# Schematic2_second.net
KiCad netlist of a schematic drawn in Altium Designer
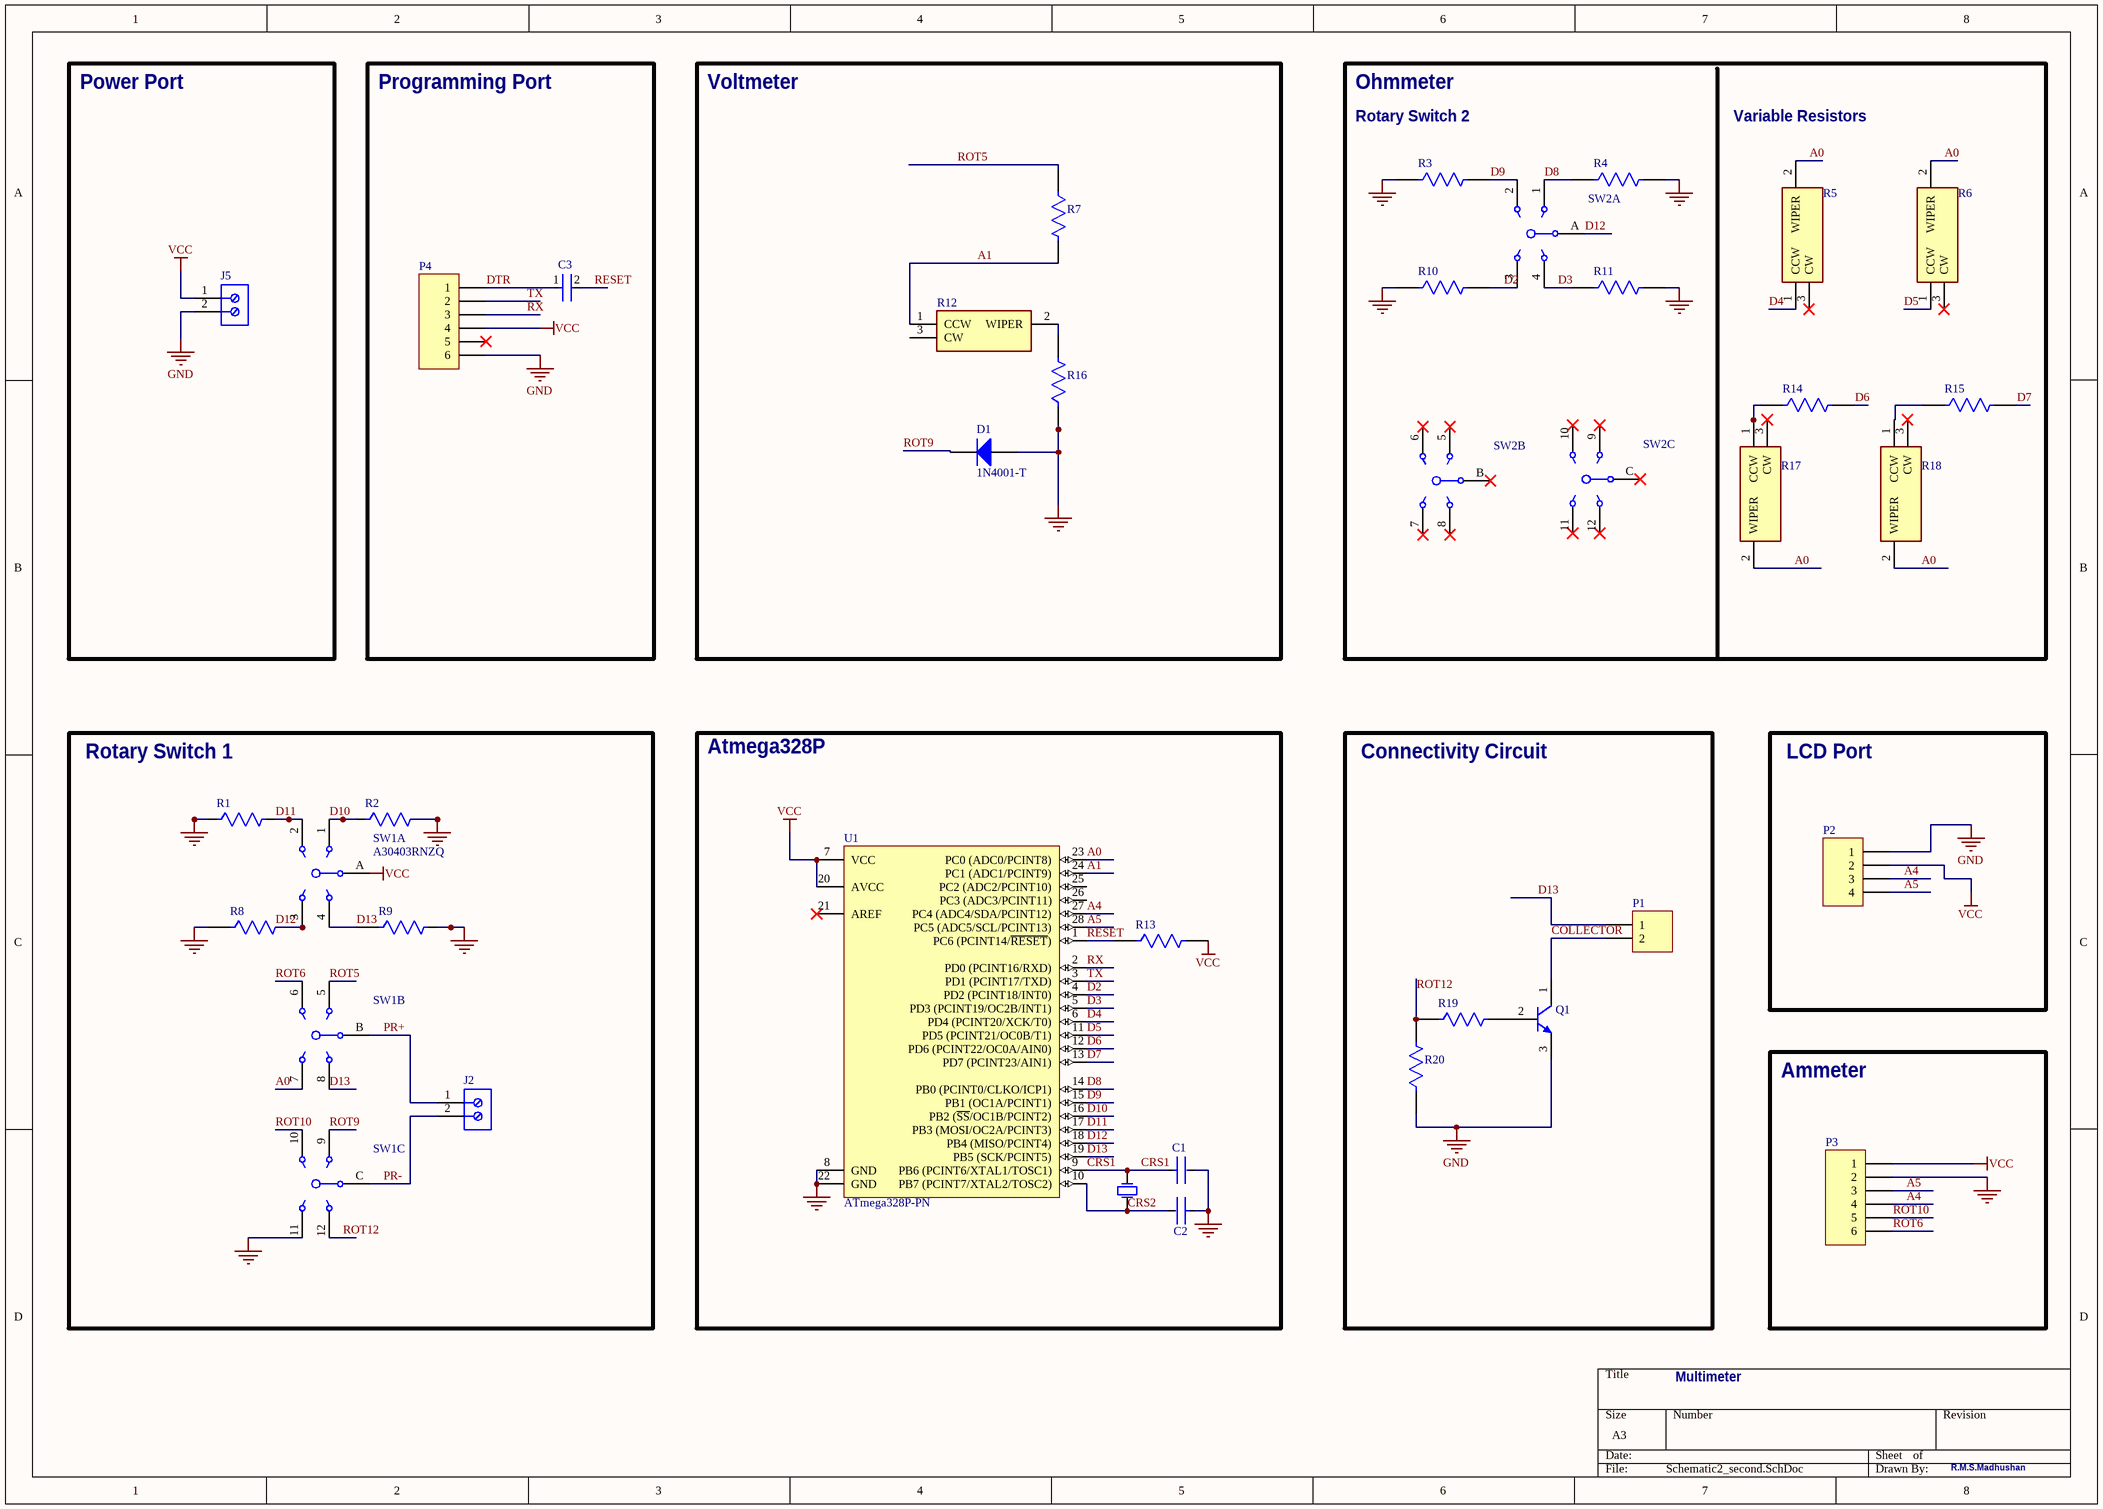
[diagram p0: Schematic2_second.SchDoc]

(export (version "E")
  (design (tool "Eeschema 10.0.6"))
  (components
    (comp (ref "C1")
      (value "RDE5C1H220J0K1H03B")
      (footprint "FP-RDE0M1-MFG")
      (description "Ceramic Capacitor 22pF ±5% 50V C0G Radial")
      (fields (field (name "TOLERANCE") "5%"))
      (libsource (lib "") (part "b4654b650e69147ec39a6b967a45e02_1"))
    )
    (comp (ref "C2")
      (value "RDE5C1H220J0K1H03B")
      (footprint "FP-RDE0M1-MFG")
      (description "Ceramic Capacitor 22pF ±5% 50V C0G Radial")
      (fields (field (name "TOLERANCE") "5%"))
      (libsource (lib "") (part "b4654b650e69147ec39a6b967a45e02_1"))
    )
    (comp (ref "C3")
      (value "RDE5C1H220J0K1H03B")
      (footprint "FP-RDE0M1-MFG")
      (description "Ceramic Capacitor 22pF ±5% 50V C0G Radial")
      (fields (field (name "TOLERANCE") "5%"))
      (libsource (lib "Altium Content Vault") (part "b4654b650e69147ec39a6b967a45e02"))
    )
    (comp (ref "D1")
      (value "1N4001-T")
      (footprint "DIOD-DO-41-P-2_V")
      (description "1.0 A Rectifier, 15 pF, 50 V, -65 to 150 degC, 2-Pin DO-41 Plastic, RoHS, Tape and Reel")
      (fields (field (name "MANUFACTURER") "Diodes Inc"))
      (libsource (lib "Altium Content Vault") (part "DIOD-D-A1K2-2"))
    )
    (comp (ref "J2")
      (value "691214110002")
      (footprint "691214110002")
      (description "Serie 2141 - 3.50 mm Horizontal Entry Modular with Rising Cage Clamp WR-TBL, 2 pin")
      (fields (field (name "MANUFACTURER") "Wurth Elektronik") (field (name "PUBLISHER") "WurthElektronik"))
      (libsource (lib "Altium Content Vault") (part "WE-CN-1P-F-TB2"))
    )
    (comp (ref "J5")
      (value "691214110002")
      (footprint "691214110002")
      (description "Serie 2141 - 3.50 mm Horizontal Entry Modular with Rising Cage Clamp WR-TBL, 2 pin")
      (fields (field (name "MANUFACTURER") "Wurth Elektronik") (field (name "PUBLISHER") "WurthElektronik"))
      (libsource (lib "Altium Content Vault") (part "WE-CN-1P-F-TB2"))
    )
    (comp (ref "P1")
      (value "Header 2")
      (footprint "MY_FE02W")
      (description "Header, 2-Pin")
      (fields (field (name "ASID PART NUMBER") "Header 2-AS"))
      (libsource (lib "Mylib+Rev+4") (part "Header 2"))
    )
    (comp (ref "P2")
      (value "Header 4")
      (footprint "MY_FE04W")
      (description "Header, 4-Pin")
      (fields (field (name "ASID PART NUMBER") "Header 4-AS"))
      (libsource (lib "Mylib+Rev+4") (part "Header 4"))
    )
    (comp (ref "P3")
      (value "Header 6")
      (footprint "MY_FE06W")
      (description "Header, 6-Pin")
      (fields (field (name "ASID PART NUMBER") "Header 6-AS"))
      (libsource (lib "Mylib+Rev+4") (part "Header 6"))
    )
    (comp (ref "P4")
      (value "Header 6")
      (footprint "MY_FE06W")
      (description "Header, 6-Pin")
      (fields (field (name "ASID PART NUMBER") "Header 6-AS"))
      (libsource (lib "Mylib+Rev+4") (part "Header 6"))
    )
    (comp (ref "Q1")
      (value "BC547BRL1G")
      (footprint "ONSC-TO-92-3-29-11_AM_BL")
      (description "Amplifier Transistor, NPN Silicon, 3-Pin TO-92, Pb-Free, Tape and Reel")
      (fields (field (name "MANUFACTURER") "On Semiconductor"))
      (libsource (lib "Altium Content Vault") (part "ONSC-NPN-C1B2E3-3"))
    )
    (comp (ref "R1")
      (value "G001R1000FE1280")
      (footprint "FP-G001R1000FE1280-MFG")
      (description "Res Wirewound 0.1 Ohm 1% 1W ±90ppm/°C Ceramic Hi Temp Sil AXL Thru-Hole Bulk")
      (fields (field (name "TOLERANCE") "1%"))
      (libsource (lib "Altium Content Vault") (part "1029c3af85768c4190bb7ad29bc67b5"))
    )
    (comp (ref "R2")
      (value "G001R1000FE1280")
      (footprint "FP-G001R1000FE1280-MFG")
      (description "Res Wirewound 0.1 Ohm 1% 1W ±90ppm/°C Ceramic Hi Temp Sil AXL Thru-Hole Bulk")
      (fields (field (name "TOLERANCE") "1%"))
      (libsource (lib "Altium Content Vault") (part "1029c3af85768c4190bb7ad29bc67b5"))
    )
    (comp (ref "R3")
      (value "G001R1000FE1280")
      (footprint "FP-G001R1000FE1280-MFG")
      (description "Res Wirewound 0.1 Ohm 1% 1W ±90ppm/°C Ceramic Hi Temp Sil AXL Thru-Hole Bulk")
      (fields (field (name "TOLERANCE") "1%"))
      (libsource (lib "Altium Content Vault") (part "1029c3af85768c4190bb7ad29bc67b5"))
    )
    (comp (ref "R4")
      (value "G001R1000FE1280")
      (footprint "FP-G001R1000FE1280-MFG")
      (description "Res Wirewound 0.1 Ohm 1% 1W ±90ppm/°C Ceramic Hi Temp Sil AXL Thru-Hole Bulk")
      (fields (field (name "TOLERANCE") "1%"))
      (libsource (lib "Altium Content Vault") (part "1029c3af85768c4190bb7ad29bc67b5"))
    )
    (comp (ref "R5")
      (value "3362P-1-203LF")
      (footprint "SamacSys:3362P_1")
      (description "Resistor")
      (fields (field (name "MOUSER PART NUMBER") "652-3362P-1-203LF"))
      (libsource (lib "*") (part "3362P-1-203LF"))
    )
    (comp (ref "R6")
      (value "3362P-1-203LF")
      (footprint "SamacSys:3362P_1")
      (description "Resistor")
      (fields (field (name "MOUSER PART NUMBER") "652-3362P-1-203LF"))
      (libsource (lib "*") (part "3362P-1-203LF"))
    )
    (comp (ref "R7")
      (value "G001R1000FE1280")
      (footprint "FP-G001R1000FE1280-MFG")
      (description "Res Wirewound 0.1 Ohm 1% 1W ±90ppm/°C Ceramic Hi Temp Sil AXL Thru-Hole Bulk")
      (fields (field (name "TOLERANCE") "1%"))
      (libsource (lib "Altium Content Vault") (part "1029c3af85768c4190bb7ad29bc67b5"))
    )
    (comp (ref "R8")
      (value "G001R1000FE1280")
      (footprint "FP-G001R1000FE1280-MFG")
      (description "Res Wirewound 0.1 Ohm 1% 1W ±90ppm/°C Ceramic Hi Temp Sil AXL Thru-Hole Bulk")
      (fields (field (name "TOLERANCE") "1%"))
      (libsource (lib "Altium Content Vault") (part "1029c3af85768c4190bb7ad29bc67b5"))
    )
    (comp (ref "R9")
      (value "G001R1000FE1280")
      (footprint "FP-G001R1000FE1280-MFG")
      (description "Res Wirewound 0.1 Ohm 1% 1W ±90ppm/°C Ceramic Hi Temp Sil AXL Thru-Hole Bulk")
      (fields (field (name "TOLERANCE") "1%"))
      (libsource (lib "Altium Content Vault") (part "1029c3af85768c4190bb7ad29bc67b5"))
    )
    (comp (ref "R10")
      (value "G001R1000FE1280")
      (footprint "FP-G001R1000FE1280-MFG")
      (description "Res Wirewound 0.1 Ohm 1% 1W ±90ppm/°C Ceramic Hi Temp Sil AXL Thru-Hole Bulk")
      (fields (field (name "TOLERANCE") "1%"))
      (libsource (lib "Altium Content Vault") (part "1029c3af85768c4190bb7ad29bc67b5"))
    )
    (comp (ref "R11")
      (value "G001R1000FE1280")
      (footprint "FP-G001R1000FE1280-MFG")
      (description "Res Wirewound 0.1 Ohm 1% 1W ±90ppm/°C Ceramic Hi Temp Sil AXL Thru-Hole Bulk")
      (fields (field (name "TOLERANCE") "1%"))
      (libsource (lib "Altium Content Vault") (part "1029c3af85768c4190bb7ad29bc67b5"))
    )
    (comp (ref "R12")
      (value "3362P-1-203LF")
      (footprint "SamacSys:3362P_1")
      (description "Resistor")
      (fields (field (name "MOUSER PART NUMBER") "652-3362P-1-203LF"))
      (libsource (lib "") (part "3362P-1-203LF_2"))
    )
    (comp (ref "R13")
      (value "G001R1000FE1280")
      (footprint "FP-G001R1000FE1280-MFG")
      (description "Res Wirewound 0.1 Ohm 1% 1W ±90ppm/°C Ceramic Hi Temp Sil AXL Thru-Hole Bulk")
      (fields (field (name "TOLERANCE") "1%"))
      (libsource (lib "Altium Content Vault") (part "1029c3af85768c4190bb7ad29bc67b5"))
    )
    (comp (ref "R14")
      (value "G001R1000FE1280")
      (footprint "FP-G001R1000FE1280-MFG")
      (description "Res Wirewound 0.1 Ohm 1% 1W ±90ppm/°C Ceramic Hi Temp Sil AXL Thru-Hole Bulk")
      (fields (field (name "TOLERANCE") "1%"))
      (libsource (lib "Altium Content Vault") (part "1029c3af85768c4190bb7ad29bc67b5"))
    )
    (comp (ref "R15")
      (value "G001R1000FE1280")
      (footprint "FP-G001R1000FE1280-MFG")
      (description "Res Wirewound 0.1 Ohm 1% 1W ±90ppm/°C Ceramic Hi Temp Sil AXL Thru-Hole Bulk")
      (fields (field (name "TOLERANCE") "1%"))
      (libsource (lib "Altium Content Vault") (part "1029c3af85768c4190bb7ad29bc67b5"))
    )
    (comp (ref "R16")
      (value "G001R1000FE1280")
      (footprint "FP-G001R1000FE1280-MFG")
      (description "Res Wirewound 0.1 Ohm 1% 1W ±90ppm/°C Ceramic Hi Temp Sil AXL Thru-Hole Bulk")
      (fields (field (name "TOLERANCE") "1%"))
      (libsource (lib "Altium Content Vault") (part "1029c3af85768c4190bb7ad29bc67b5"))
    )
    (comp (ref "R17")
      (value "3362P-1-203LF")
      (footprint "SamacSys:3362P_1")
      (description "Resistor")
      (fields (field (name "MOUSER PART NUMBER") "652-3362P-1-203LF"))
      (libsource (lib "") (part "3362P-1-203LF_1"))
    )
    (comp (ref "R18")
      (value "3362P-1-203LF")
      (footprint "SamacSys:3362P_1")
      (description "Resistor")
      (fields (field (name "MOUSER PART NUMBER") "652-3362P-1-203LF"))
      (libsource (lib "") (part "3362P-1-203LF_1"))
    )
    (comp (ref "R19")
      (value "G001R1000FE1280")
      (footprint "FP-G001R1000FE1280-MFG")
      (description "Res Wirewound 0.1 Ohm 1% 1W ±90ppm/°C Ceramic Hi Temp Sil AXL Thru-Hole Bulk")
      (fields (field (name "TOLERANCE") "1%"))
      (libsource (lib "Altium Content Vault") (part "1029c3af85768c4190bb7ad29bc67b5"))
    )
    (comp (ref "R20")
      (value "G001R1000FE1280")
      (footprint "FP-G001R1000FE1280-MFG")
      (description "Res Wirewound 0.1 Ohm 1% 1W ±90ppm/°C Ceramic Hi Temp Sil AXL Thru-Hole Bulk")
      (fields (field (name "TOLERANCE") "1%"))
      (libsource (lib "Altium Content Vault") (part "1029c3af85768c4190bb7ad29bc67b5"))
    )
    (comp (ref "SW1")
      (value "A30403RNZQ")
      (footprint "CKCP-A30403RNZQ-15_V")
      (description "A Series Rotary Switch, 3 Poles, 4 Positions, 30 deg Angle of Throw, -30 to 85 degC, RoHS")
      (fields (field (name "MANUFACTURER") "C&K Components"))
      (libsource (lib "Altium Content Vault") (part "CKCP-SW_3P4T-15"))
    )
    (comp (ref "SW2")
      (value "A30403RNZQ")
      (footprint "CKCP-A30403RNZQ-15_V")
      (description "A Series Rotary Switch, 3 Poles, 4 Positions, 30 deg Angle of Throw, -30 to 85 degC, RoHS")
      (fields (field (name "MANUFACTURER") "C&K Components"))
      (libsource (lib "Altium Content Vault") (part "CKCP-SW_3P4T-15"))
    )
    (comp (ref "U1")
      (value "ATmega328P-PN")
      (footprint "28P3")
      (libsource (lib "Altium Content Vault") (part "MC-8B-ATM48-IL28"))
    )
    (comp (ref "Y1")
      (value "FOXSLF/160-20")
      (footprint "FOX-FOXSLF160-20")
      (description "Resistance Weld Thru-Hole Crystal, 16 MHz, -20 to 70 degC, 2-Pin THD, RoHS, Bulk")
      (fields (field (name "TOLERANCE") "1%"))
      (libsource (lib "Altium Content Vault") (part "XTAL-1-2-2"))
    )
  )
  (nets
    (net (code "2") (name "/A0") (class "Default")
      (node (ref "R17") (pin "2") (pinfunction "WIPER_2") (pintype "passive"))
      (node (ref "R18") (pin "2") (pinfunction "WIPER_2") (pintype "passive"))
      (node (ref "R5") (pin "2") (pinfunction "WIPER_2") (pintype "passive"))
      (node (ref "R6") (pin "2") (pinfunction "WIPER_2") (pintype "passive"))
      (node (ref "SW1") (pin "7") (pinfunction "7_7") (pintype "passive"))
      (node (ref "U1") (pin "23") (pinfunction "PC0_(ADC0/PCINT8)_23") (pintype "bidirectional"))
    )
    (net (code "3") (name "/A1") (class "Default")
      (node (ref "R12") (pin "1") (pinfunction "CCW_1") (pintype "passive"))
      (node (ref "R7") (pin "2") (pinfunction "2_2") (pintype "passive"))
      (node (ref "U1") (pin "24") (pinfunction "PC1_(ADC1/PCINT9)_24") (pintype "bidirectional"))
    )
    (net (code "4") (name "/A4") (class "Default")
      (node (ref "P2") (pin "3") (pinfunction "3_3") (pintype "passive"))
      (node (ref "P3") (pin "4") (pinfunction "4_4") (pintype "passive"))
      (node (ref "U1") (pin "27") (pinfunction "PC4_(ADC4/SDA/PCINT12)_27") (pintype "bidirectional"))
    )
    (net (code "5") (name "/A5") (class "Default")
      (node (ref "P2") (pin "4") (pinfunction "4_4") (pintype "passive"))
      (node (ref "P3") (pin "3") (pinfunction "3_3") (pintype "passive"))
      (node (ref "U1") (pin "28") (pinfunction "PC5_(ADC5/SCL/PCINT13)_28") (pintype "bidirectional"))
    )
    (net (code "6") (name "/COLLECTOR") (class "Default")
      (node (ref "P1") (pin "2") (pinfunction "2_2") (pintype "passive"))
      (node (ref "Q1") (pin "1") (pinfunction "C_1") (pintype "passive"))
    )
    (net (code "7") (name "/CRS1") (class "Default")
      (node (ref "C1") (pin "1") (pinfunction "1_1") (pintype "passive"))
      (node (ref "U1") (pin "9") (pinfunction "PB6_(PCINT6/XTAL1/TOSC1)_9") (pintype "bidirectional"))
      (node (ref "Y1") (pin "1") (pinfunction "1_1") (pintype "passive"))
    )
    (net (code "8") (name "/CRS2") (class "Default")
      (node (ref "C2") (pin "2") (pinfunction "2_2") (pintype "passive"))
      (node (ref "U1") (pin "10") (pinfunction "PB7_(PCINT7/XTAL2/TOSC2)_10") (pintype "bidirectional"))
      (node (ref "Y1") (pin "2") (pinfunction "2_2") (pintype "passive"))
    )
    (net (code "9") (name "/D2") (class "Default")
      (node (ref "R10") (pin "2") (pinfunction "2_2") (pintype "passive"))
      (node (ref "SW2") (pin "3") (pinfunction "3_3") (pintype "passive"))
      (node (ref "U1") (pin "4") (pinfunction "PD2_(PCINT18/INT0)_4") (pintype "bidirectional"))
    )
    (net (code "10") (name "/D3") (class "Default")
      (node (ref "R11") (pin "1") (pinfunction "1_1") (pintype "passive"))
      (node (ref "SW2") (pin "4") (pinfunction "4_4") (pintype "passive"))
      (node (ref "U1") (pin "5") (pinfunction "PD3_(PCINT19/OC2B/INT1)_5") (pintype "bidirectional"))
    )
    (net (code "11") (name "/D4") (class "Default")
      (node (ref "R5") (pin "1") (pinfunction "CCW_1") (pintype "passive"))
      (node (ref "U1") (pin "6") (pinfunction "PD4_(PCINT20/XCK/T0)_6") (pintype "bidirectional"))
    )
    (net (code "12") (name "/D5") (class "Default")
      (node (ref "R6") (pin "1") (pinfunction "CCW_1") (pintype "passive"))
      (node (ref "U1") (pin "11") (pinfunction "PD5_(PCINT21/OC0B/T1)_11") (pintype "bidirectional"))
    )
    (net (code "13") (name "/D6") (class "Default")
      (node (ref "R14") (pin "2") (pinfunction "2_2") (pintype "passive"))
      (node (ref "U1") (pin "12") (pinfunction "PD6_(PCINT22/OC0A/AIN0)_12") (pintype "bidirectional"))
    )
    (net (code "14") (name "/D7") (class "Default")
      (node (ref "R15") (pin "2") (pinfunction "2_2") (pintype "passive"))
      (node (ref "U1") (pin "13") (pinfunction "PD7_(PCINT23/AIN1)_13") (pintype "bidirectional"))
    )
    (net (code "15") (name "/D8") (class "Default")
      (node (ref "R4") (pin "1") (pinfunction "1_1") (pintype "passive"))
      (node (ref "SW2") (pin "1") (pinfunction "1_1") (pintype "passive"))
      (node (ref "U1") (pin "14") (pinfunction "PB0_(PCINT0/CLKO/ICP1)_14") (pintype "bidirectional"))
    )
    (net (code "16") (name "/D9") (class "Default")
      (node (ref "R3") (pin "2") (pinfunction "2_2") (pintype "passive"))
      (node (ref "SW2") (pin "2") (pinfunction "2_2") (pintype "passive"))
      (node (ref "U1") (pin "15") (pinfunction "PB1_(OC1A/PCINT1)_15") (pintype "bidirectional"))
    )
    (net (code "17") (name "/D10") (class "Default")
      (node (ref "R2") (pin "1") (pinfunction "1_1") (pintype "passive"))
      (node (ref "SW1") (pin "1") (pinfunction "1_1") (pintype "passive"))
      (node (ref "U1") (pin "16") (pinfunction "PB2_(~{SS}/OC1B/PCINT2)_16") (pintype "bidirectional"))
    )
    (net (code "18") (name "/D11") (class "Default")
      (node (ref "R1") (pin "2") (pinfunction "2_2") (pintype "passive"))
      (node (ref "SW1") (pin "2") (pinfunction "2_2") (pintype "passive"))
      (node (ref "U1") (pin "17") (pinfunction "PB3_(MOSI/OC2A/PCINT3)_17") (pintype "bidirectional"))
    )
    (net (code "19") (name "/D12") (class "Default")
      (node (ref "R8") (pin "2") (pinfunction "2_2") (pintype "passive"))
      (node (ref "SW1") (pin "3") (pinfunction "3_3") (pintype "passive"))
      (node (ref "SW2") (pin "A") (pinfunction "A_A") (pintype "passive"))
      (node (ref "U1") (pin "18") (pinfunction "PB4_(MISO/PCINT4)_18") (pintype "bidirectional"))
    )
    (net (code "20") (name "/D13") (class "Default")
      (node (ref "P1") (pin "1") (pinfunction "1_1") (pintype "passive"))
      (node (ref "R9") (pin "1") (pinfunction "1_1") (pintype "passive"))
      (node (ref "SW1") (pin "4") (pinfunction "4_4") (pintype "passive"))
      (node (ref "SW1") (pin "8") (pinfunction "8_8") (pintype "passive"))
      (node (ref "U1") (pin "19") (pinfunction "PB5_(SCK/PCINT5)_19") (pintype "bidirectional"))
    )
    (net (code "21") (name "/DTR") (class "Default")
      (node (ref "C3") (pin "1") (pinfunction "1_1") (pintype "passive"))
      (node (ref "P4") (pin "1") (pinfunction "1_1") (pintype "passive"))
    )
    (net (code "22") (name "/PR+") (class "Default")
      (node (ref "J2") (pin "1") (pinfunction "1_1") (pintype "passive"))
      (node (ref "SW1") (pin "B") (pinfunction "B_B") (pintype "passive"))
    )
    (net (code "23") (name "/PR-") (class "Default")
      (node (ref "J2") (pin "2") (pinfunction "2_2") (pintype "passive"))
      (node (ref "SW1") (pin "C") (pinfunction "C_C") (pintype "passive"))
    )
    (net (code "24") (name "/RESET") (class "Default")
      (node (ref "C3") (pin "2") (pinfunction "2_2") (pintype "passive"))
      (node (ref "R13") (pin "1") (pinfunction "1_1") (pintype "passive"))
      (node (ref "U1") (pin "1") (pinfunction "PC6_(PCINT14/~{RESET})_1") (pintype "bidirectional"))
    )
    (net (code "25") (name "/ROT5") (class "Default")
      (node (ref "R7") (pin "1") (pinfunction "1_1") (pintype "passive"))
      (node (ref "SW1") (pin "5") (pinfunction "5_5") (pintype "passive"))
    )
    (net (code "26") (name "/ROT6") (class "Default")
      (node (ref "P3") (pin "6") (pinfunction "6_6") (pintype "passive"))
      (node (ref "SW1") (pin "6") (pinfunction "6_6") (pintype "passive"))
    )
    (net (code "27") (name "/ROT9") (class "Default")
      (node (ref "D1") (pin "2") (pinfunction "K_2") (pintype "passive"))
      (node (ref "SW1") (pin "9") (pinfunction "9_9") (pintype "passive"))
    )
    (net (code "28") (name "/ROT10") (class "Default")
      (node (ref "P3") (pin "5") (pinfunction "5_5") (pintype "passive"))
      (node (ref "SW1") (pin "10") (pinfunction "10_10") (pintype "passive"))
    )
    (net (code "29") (name "/ROT12") (class "Default")
      (node (ref "R19") (pin "1") (pinfunction "1_1") (pintype "passive"))
      (node (ref "R20") (pin "2") (pinfunction "2_2") (pintype "passive"))
      (node (ref "SW1") (pin "12") (pinfunction "12_12") (pintype "passive"))
    )
    (net (code "30") (name "/RX") (class "Default")
      (node (ref "P4") (pin "3") (pinfunction "3_3") (pintype "passive"))
      (node (ref "U1") (pin "2") (pinfunction "PD0_(PCINT16/RXD)_2") (pintype "bidirectional"))
    )
    (net (code "31") (name "/TX") (class "Default")
      (node (ref "P4") (pin "2") (pinfunction "2_2") (pintype "passive"))
      (node (ref "U1") (pin "3") (pinfunction "PD1_(PCINT17/TXD)_3") (pintype "bidirectional"))
    )
    (net (code "32") (name "GND") (class "Default")
      (node (ref "C1") (pin "2") (pinfunction "2_2") (pintype "passive"))
      (node (ref "C2") (pin "1") (pinfunction "1_1") (pintype "passive"))
      (node (ref "D1") (pin "1") (pinfunction "A_1") (pintype "passive"))
      (node (ref "J5") (pin "2") (pinfunction "2_2") (pintype "passive"))
      (node (ref "P2") (pin "1") (pinfunction "1_1") (pintype "passive"))
      (node (ref "P3") (pin "2") (pinfunction "2_2") (pintype "passive"))
      (node (ref "P4") (pin "6") (pinfunction "6_6") (pintype "passive"))
      (node (ref "Q1") (pin "3") (pinfunction "E_3") (pintype "passive"))
      (node (ref "R1") (pin "1") (pinfunction "1_1") (pintype "passive"))
      (node (ref "R10") (pin "1") (pinfunction "1_1") (pintype "passive"))
      (node (ref "R11") (pin "2") (pinfunction "2_2") (pintype "passive"))
      (node (ref "R16") (pin "1") (pinfunction "1_1") (pintype "passive"))
      (node (ref "R2") (pin "2") (pinfunction "2_2") (pintype "passive"))
      (node (ref "R20") (pin "1") (pinfunction "1_1") (pintype "passive"))
      (node (ref "R3") (pin "1") (pinfunction "1_1") (pintype "passive"))
      (node (ref "R4") (pin "2") (pinfunction "2_2") (pintype "passive"))
      (node (ref "R8") (pin "1") (pinfunction "1_1") (pintype "passive"))
      (node (ref "R9") (pin "2") (pinfunction "2_2") (pintype "passive"))
      (node (ref "SW1") (pin "11") (pinfunction "11_11") (pintype "passive"))
      (node (ref "U1") (pin "22") (pinfunction "GND_22") (pintype "power_in"))
      (node (ref "U1") (pin "8") (pinfunction "GND_8") (pintype "power_in"))
    )
    (net (code "33") (name "Net-(Q1-B)") (class "Default")
      (node (ref "Q1") (pin "2") (pinfunction "B_2") (pintype "passive"))
      (node (ref "R19") (pin "2") (pinfunction "2_2") (pintype "passive"))
    )
    (net (code "34") (name "Net-(R12-WIPER)") (class "Default")
      (node (ref "R12") (pin "2") (pinfunction "WIPER_2") (pintype "passive"))
      (node (ref "R16") (pin "2") (pinfunction "2_2") (pintype "passive"))
    )
    (net (code "35") (name "Net-(R17-CCW)") (class "Default")
      (node (ref "R14") (pin "1") (pinfunction "1_1") (pintype "passive"))
      (node (ref "R17") (pin "1") (pinfunction "CCW_1") (pintype "passive"))
    )
    (net (code "36") (name "Net-(R18-CCW)") (class "Default")
      (node (ref "R15") (pin "1") (pinfunction "1_1") (pintype "passive"))
      (node (ref "R18") (pin "1") (pinfunction "CCW_1") (pintype "passive"))
    )
    (net (code "37") (name "VCC") (class "Default")
      (node (ref "J5") (pin "1") (pinfunction "1_1") (pintype "passive"))
      (node (ref "P2") (pin "2") (pinfunction "2_2") (pintype "passive"))
      (node (ref "P3") (pin "1") (pinfunction "1_1") (pintype "passive"))
      (node (ref "P4") (pin "4") (pinfunction "4_4") (pintype "passive"))
      (node (ref "R13") (pin "2") (pinfunction "2_2") (pintype "passive"))
      (node (ref "SW1") (pin "A") (pinfunction "A_A") (pintype "passive"))
      (node (ref "U1") (pin "20") (pinfunction "AVCC_20") (pintype "power_in"))
      (node (ref "U1") (pin "7") (pinfunction "VCC_7") (pintype "power_in"))
    )
    (net (code "38") (name "unconnected-(P4-Pad5)") (class "Default")
      (node (ref "P4") (pin "5") (pinfunction "5_5") (pintype "passive+no_connect"))
    )
    (net (code "39") (name "unconnected-(R5-CW-Pad3)") (class "Default")
      (node (ref "R5") (pin "3") (pinfunction "CW_3") (pintype "passive+no_connect"))
    )
    (net (code "40") (name "unconnected-(R6-CW-Pad3)") (class "Default")
      (node (ref "R6") (pin "3") (pinfunction "CW_3") (pintype "passive+no_connect"))
    )
    (net (code "41") (name "unconnected-(R12-CW-Pad3)") (class "Default")
      (node (ref "R12") (pin "3") (pinfunction "CW_3") (pintype "passive"))
    )
    (net (code "42") (name "unconnected-(R17-CW-Pad3)") (class "Default")
      (node (ref "R17") (pin "3") (pinfunction "CW_3") (pintype "passive+no_connect"))
    )
    (net (code "43") (name "unconnected-(R18-CW-Pad3)") (class "Default")
      (node (ref "R18") (pin "3") (pinfunction "CW_3") (pintype "passive+no_connect"))
    )
    (net (code "44") (name "unconnected-(SW2-Pad5)") (class "Default")
      (node (ref "SW2") (pin "5") (pinfunction "5_5") (pintype "passive+no_connect"))
    )
    (net (code "45") (name "unconnected-(SW2-Pad6)") (class "Default")
      (node (ref "SW2") (pin "6") (pinfunction "6_6") (pintype "passive+no_connect"))
    )
    (net (code "46") (name "unconnected-(SW2-Pad7)") (class "Default")
      (node (ref "SW2") (pin "7") (pinfunction "7_7") (pintype "passive+no_connect"))
    )
    (net (code "47") (name "unconnected-(SW2-Pad8)") (class "Default")
      (node (ref "SW2") (pin "8") (pinfunction "8_8") (pintype "passive+no_connect"))
    )
    (net (code "48") (name "unconnected-(SW2-Pad9)") (class "Default")
      (node (ref "SW2") (pin "9") (pinfunction "9_9") (pintype "passive+no_connect"))
    )
    (net (code "49") (name "unconnected-(SW2-Pad10)") (class "Default")
      (node (ref "SW2") (pin "10") (pinfunction "10_10") (pintype "passive+no_connect"))
    )
    (net (code "50") (name "unconnected-(SW2-Pad11)") (class "Default")
      (node (ref "SW2") (pin "11") (pinfunction "11_11") (pintype "passive+no_connect"))
    )
    (net (code "51") (name "unconnected-(SW2-Pad12)") (class "Default")
      (node (ref "SW2") (pin "12") (pinfunction "12_12") (pintype "passive+no_connect"))
    )
    (net (code "52") (name "unconnected-(SW2-PadB)") (class "Default")
      (node (ref "SW2") (pin "B") (pinfunction "B_B") (pintype "passive+no_connect"))
    )
    (net (code "53") (name "unconnected-(SW2-PadC)") (class "Default")
      (node (ref "SW2") (pin "C") (pinfunction "C_C") (pintype "passive+no_connect"))
    )
    (net (code "54") (name "unconnected-(U1-AREF-Pad21)") (class "Default")
      (node (ref "U1") (pin "21") (pinfunction "AREF_21") (pintype "power_in+no_connect"))
    )
    (net (code "55") (name "unconnected-(U1-PC2_(ADC2{slash}PCINT10)-Pad25)") (class "Default")
      (node (ref "U1") (pin "25") (pinfunction "PC2_(ADC2/PCINT10)_25") (pintype "bidirectional"))
    )
    (net (code "56") (name "unconnected-(U1-PC3_(ADC3{slash}PCINT11)-Pad26)") (class "Default")
      (node (ref "U1") (pin "26") (pinfunction "PC3_(ADC3/PCINT11)_26") (pintype "bidirectional"))
    )
  )
)
